# SPM.net
KiCad netlist of a schematic drawn in EAGLE
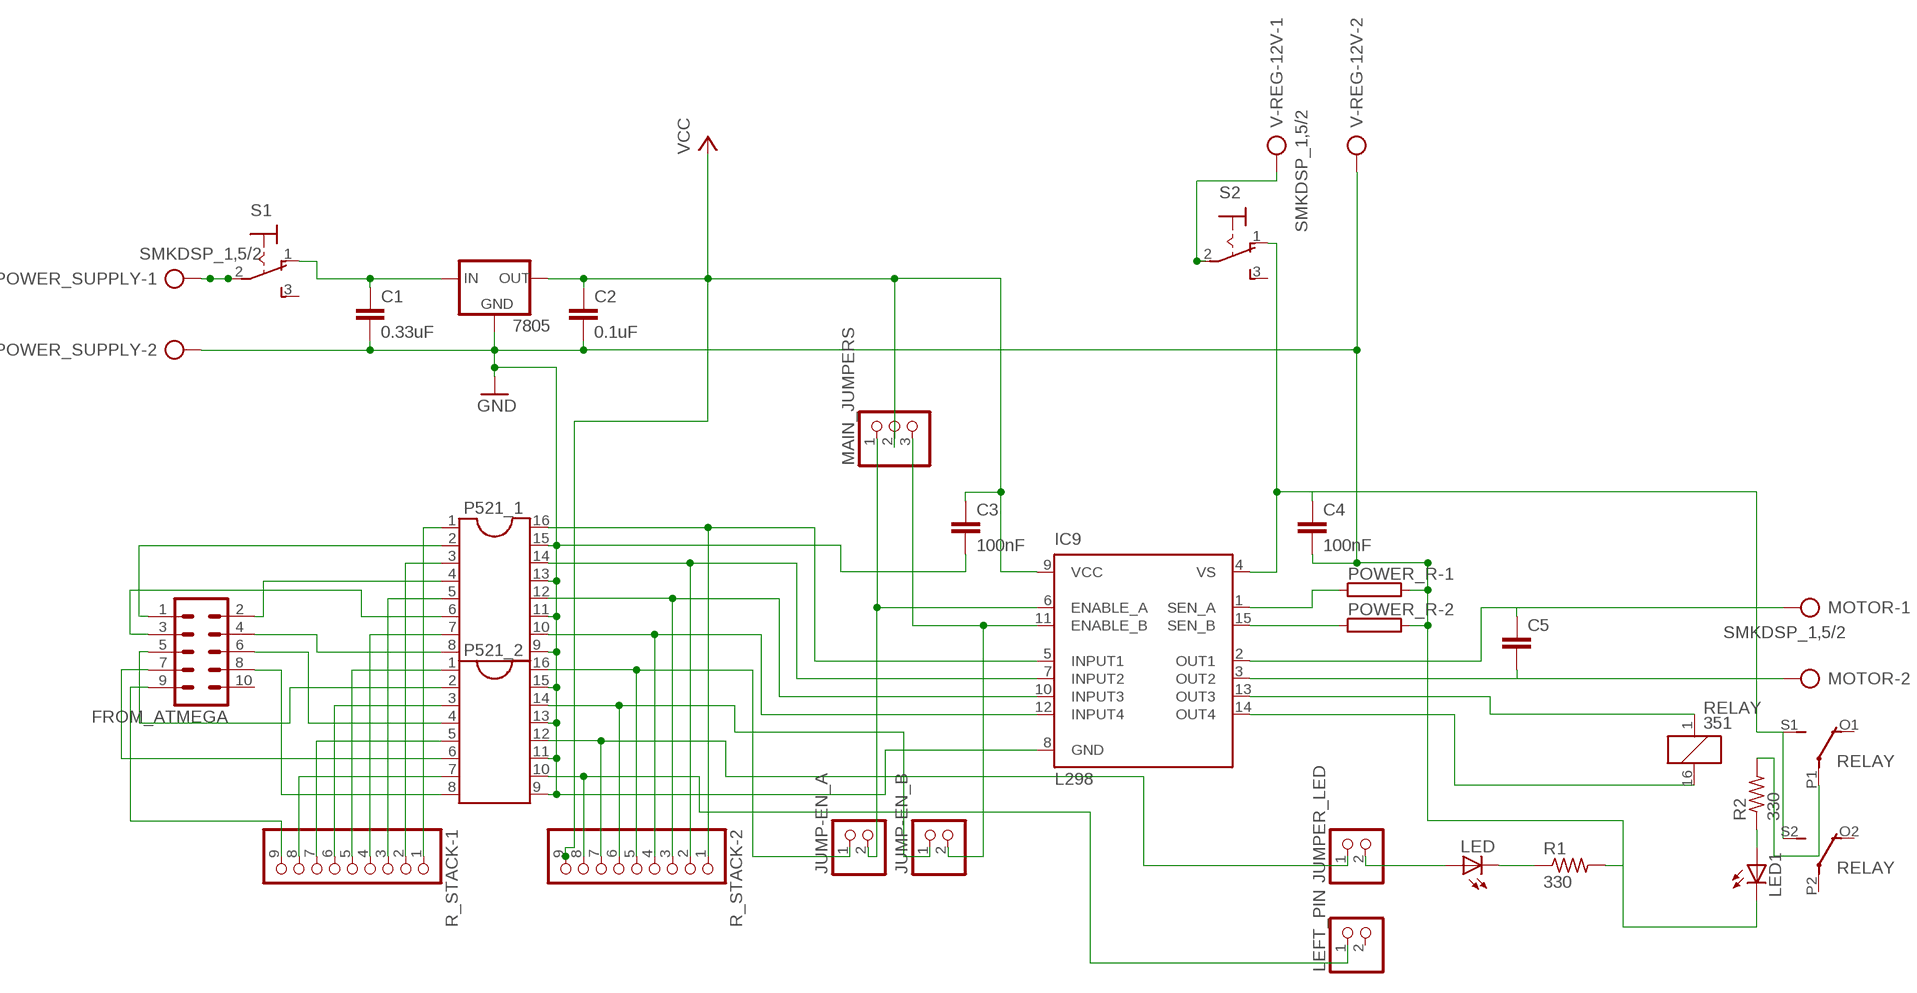
[diagram p0: schematic, sheet 1]

(export (version "E")
  (design (tool "Eeschema 10.0.6"))
  (components
    (comp (ref "7805")
      (value "78XXS")
      (footprint "eagle-import:78XXS")
      (libsource (lib "eagle-import") (part "78XXS"))
    )
    (comp (ref "C1")
      (value "0.33uF")
      (footprint "eagle-import:C2.5-3")
      (libsource (lib "eagle-import") (part "C2,5-3"))
    )
    (comp (ref "C2")
      (value "0.1uF")
      (footprint "eagle-import:C2.5-3")
      (libsource (lib "eagle-import") (part "C2,5-3"))
    )
    (comp (ref "C3")
      (value "100nF")
      (footprint "eagle-import:C2.5-3")
      (libsource (lib "eagle-import") (part "C2,5-3"))
    )
    (comp (ref "C4")
      (value "100nF")
      (footprint "eagle-import:C2.5-3")
      (libsource (lib "eagle-import") (part "C2,5-3"))
    )
    (comp (ref "C5")
      (value "C2,5-3")
      (footprint "eagle-import:C2.5-3")
      (libsource (lib "eagle-import") (part "C2,5-3"))
    )
    (comp (ref "FROM_ATMEGA")
      (value "ML10")
      (footprint "eagle-import:ML10")
      (libsource (lib "eagle-import") (part "ML10"))
    )
    (comp (ref "IC9")
      (value "L298")
      (footprint "eagle-import:MULTIWATT-15")
      (fields (field (name "MPN") "L298N"))
      (libsource (lib "eagle-import") (part "L298"))
    )
    (comp (ref "JUMP-EN_A")
      (value "PINHD-1X2")
      (footprint "eagle-import:1X02")
      (libsource (lib "eagle-import") (part "PINHD-1X2"))
    )
    (comp (ref "JUMP-EN_B")
      (value "PINHD-1X2")
      (footprint "eagle-import:1X02")
      (libsource (lib "eagle-import") (part "PINHD-1X2"))
    )
    (comp (ref "JUMPER_LED")
      (value "PINHD-1X2")
      (footprint "eagle-import:1X02")
      (libsource (lib "eagle-import") (part "PINHD-1X2"))
    )
    (comp (ref "LED")
      (value "LED10MM")
      (footprint "eagle-import:LED10MM")
      (libsource (lib "eagle-import") (part "LED10MM"))
    )
    (comp (ref "LED1")
      (value "LED10MM")
      (footprint "eagle-import:LED10MM")
      (libsource (lib "eagle-import") (part "LED10MM"))
    )
    (comp (ref "LEFT_PIN")
      (value "PINHD-1X2")
      (footprint "eagle-import:1X02")
      (libsource (lib "eagle-import") (part "PINHD-1X2"))
    )
    (comp (ref "MAIN_JUMPERS")
      (value "PINHD-1X3")
      (footprint "eagle-import:1X03")
      (libsource (lib "eagle-import") (part "PINHD-1X3"))
    )
    (comp (ref "MOTOR")
      (value "SMKDSP_1,5/2")
      (footprint "eagle-import:SMKDSP_1,5_2")
      (fields (field (name "MF") "FARNELL") (field (name "MPN") "1733570"))
      (libsource (lib "eagle-import") (part "SMKDSP_1,5/2"))
    )
    (comp (ref "P521_1")
      (value "DIL16")
      (footprint "eagle-import:DIL16")
      (libsource (lib "eagle-import") (part "DIL16"))
    )
    (comp (ref "P521_2")
      (value "DIL16")
      (footprint "eagle-import:DIL16")
      (libsource (lib "eagle-import") (part "DIL16"))
    )
    (comp (ref "POWER_R-1")
      (value "RHPS932")
      (footprint "eagle-import:HPS932")
      (libsource (lib "eagle-import") (part "RHPS932"))
    )
    (comp (ref "POWER_R-2")
      (value "RHPS932")
      (footprint "eagle-import:HPS932")
      (fields (field (name "OC_FARNELL") "unknown") (field (name "OC_NEWARK") "unknown"))
      (libsource (lib "eagle-import") (part "RHPS932"))
    )
    (comp (ref "POWER_SUPPLY")
      (value "SMKDSP_1,5/2")
      (footprint "eagle-import:SMKDSP_1,5_2")
      (fields (field (name "MF") "FARNELL") (field (name "MPN") "1733570"))
      (libsource (lib "eagle-import") (part "SMKDSP_1,5/2"))
    )
    (comp (ref "R1")
      (value "330")
      (footprint "eagle-import:0204_7")
      (libsource (lib "eagle-import") (part "R-US_0204/7"))
    )
    (comp (ref "R2")
      (value "330")
      (footprint "eagle-import:0204_7")
      (libsource (lib "eagle-import") (part "R-US_0204/7"))
    )
    (comp (ref "RELAY")
      (value "351")
      (footprint "eagle-import:351")
      (libsource (lib "eagle-import") (part "351"))
    )
    (comp (ref "R_STACK-1")
      (value "PINHD-1X9")
      (footprint "eagle-import:1X09")
      (libsource (lib "eagle-import") (part "PINHD-1X9"))
    )
    (comp (ref "R_STACK-2")
      (value "PINHD-1X9")
      (footprint "eagle-import:1X09")
      (libsource (lib "eagle-import") (part "PINHD-1X9"))
    )
    (comp (ref "S1")
      (value "320-916")
      (footprint "eagle-import:320-916")
      (libsource (lib "eagle-import") (part "320-916"))
    )
    (comp (ref "S2")
      (value "320-916")
      (footprint "eagle-import:320-916")
      (libsource (lib "eagle-import") (part "320-916"))
    )
    (comp (ref "V-REG-12V")
      (value "SMKDSP_1,5/2")
      (footprint "eagle-import:SMKDSP_1,5_2")
      (fields (field (name "MF") "FARNELL") (field (name "MPN") "1733570"))
      (libsource (lib "eagle-import") (part "SMKDSP_1,5/2"))
    )
  )
  (nets
    (net (code "1") (name "GND") (class "Default")
      (node (ref "7805") (pin "GND") (pinfunction "GND_GND") (pintype "input"))
      (node (ref "C1") (pin "2") (pinfunction "2_2") (pintype "passive"))
      (node (ref "C2") (pin "2") (pinfunction "2_2") (pintype "passive"))
      (node (ref "C3") (pin "2") (pinfunction "2_2") (pintype "passive"))
      (node (ref "C4") (pin "2") (pinfunction "2_2") (pintype "passive"))
      (node (ref "IC9") (pin "8") (pinfunction "GND_8") (pintype "power_in"))
      (node (ref "LED1") (pin "K") (pinfunction "C_K") (pintype "passive"))
      (node (ref "P521_1") (pin "11") (pinfunction "11_11") (pintype "passive"))
      (node (ref "P521_1") (pin "13") (pinfunction "13_13") (pintype "passive"))
      (node (ref "P521_1") (pin "15") (pinfunction "15_15") (pintype "passive"))
      (node (ref "P521_1") (pin "9") (pinfunction "9_9") (pintype "passive"))
      (node (ref "P521_2") (pin "11") (pinfunction "11_11") (pintype "passive"))
      (node (ref "P521_2") (pin "13") (pinfunction "13_13") (pintype "passive"))
      (node (ref "P521_2") (pin "15") (pinfunction "15_15") (pintype "passive"))
      (node (ref "P521_2") (pin "9") (pinfunction "9_9") (pintype "passive"))
      (node (ref "POWER_R-1") (pin "2") (pinfunction "2_2") (pintype "passive"))
      (node (ref "POWER_R-2") (pin "2") (pinfunction "2_2") (pintype "passive"))
      (node (ref "POWER_SUPPLY") (pin "2") (pinfunction "KL_2") (pintype "passive"))
      (node (ref "R1") (pin "2") (pinfunction "2_2") (pintype "passive"))
      (node (ref "V-REG-12V") (pin "2") (pinfunction "KL_2") (pintype "passive"))
    )
    (net (code "2") (name "Net-(FROM_ATMEGA-Pad1)") (class "Default")
      (node (ref "FROM_ATMEGA") (pin "1") (pinfunction "1_1") (pintype "passive"))
      (node (ref "P521_1") (pin "2") (pinfunction "2_2") (pintype "passive"))
    )
    (net (code "3") (name "Net-(FROM_ATMEGA-Pad2)") (class "Default")
      (node (ref "FROM_ATMEGA") (pin "2") (pinfunction "2_2") (pintype "passive"))
      (node (ref "P521_1") (pin "4") (pinfunction "4_4") (pintype "passive"))
    )
    (net (code "4") (name "Net-(FROM_ATMEGA-Pad3)") (class "Default")
      (node (ref "FROM_ATMEGA") (pin "3") (pinfunction "3_3") (pintype "passive"))
      (node (ref "P521_1") (pin "6") (pinfunction "6_6") (pintype "passive"))
    )
    (net (code "5") (name "Net-(FROM_ATMEGA-Pad4)") (class "Default")
      (node (ref "FROM_ATMEGA") (pin "4") (pinfunction "4_4") (pintype "passive"))
      (node (ref "P521_1") (pin "8") (pinfunction "8_8") (pintype "passive"))
    )
    (net (code "6") (name "Net-(FROM_ATMEGA-Pad5)") (class "Default")
      (node (ref "FROM_ATMEGA") (pin "5") (pinfunction "5_5") (pintype "passive"))
      (node (ref "P521_2") (pin "2") (pinfunction "2_2") (pintype "passive"))
    )
    (net (code "7") (name "Net-(FROM_ATMEGA-Pad6)") (class "Default")
      (node (ref "FROM_ATMEGA") (pin "6") (pinfunction "6_6") (pintype "passive"))
      (node (ref "P521_2") (pin "4") (pinfunction "4_4") (pintype "passive"))
    )
    (net (code "8") (name "Net-(FROM_ATMEGA-Pad7)") (class "Default")
      (node (ref "FROM_ATMEGA") (pin "7") (pinfunction "7_7") (pintype "passive"))
      (node (ref "P521_2") (pin "6") (pinfunction "6_6") (pintype "passive"))
    )
    (net (code "9") (name "Net-(FROM_ATMEGA-Pad8)") (class "Default")
      (node (ref "FROM_ATMEGA") (pin "8") (pinfunction "8_8") (pintype "passive"))
      (node (ref "P521_2") (pin "8") (pinfunction "8_8") (pintype "passive"))
    )
    (net (code "10") (name "Net-(FROM_ATMEGA-Pad9)") (class "Default")
      (node (ref "FROM_ATMEGA") (pin "9") (pinfunction "9_9") (pintype "passive"))
      (node (ref "R_STACK-1") (pin "9") (pinfunction "9_9") (pintype "passive"))
    )
    (net (code "11") (name "Net-(IC9-ENABLE_A)") (class "Default")
      (node (ref "IC9") (pin "6") (pinfunction "ENABLE_A_6") (pintype "input"))
      (node (ref "JUMP-EN_A") (pin "2") (pinfunction "2_2") (pintype "passive"))
      (node (ref "MAIN_JUMPERS") (pin "1") (pinfunction "1_1") (pintype "passive"))
    )
    (net (code "12") (name "Net-(IC9-ENABLE_B)") (class "Default")
      (node (ref "IC9") (pin "11") (pinfunction "ENABLE_B_11") (pintype "input"))
      (node (ref "JUMP-EN_B") (pin "2") (pinfunction "2_2") (pintype "passive"))
      (node (ref "MAIN_JUMPERS") (pin "3") (pinfunction "3_3") (pintype "passive"))
    )
    (net (code "13") (name "Net-(IC9-INPUT1)") (class "Default")
      (node (ref "IC9") (pin "5") (pinfunction "INPUT1_5") (pintype "input"))
      (node (ref "P521_1") (pin "16") (pinfunction "16_16") (pintype "passive"))
      (node (ref "R_STACK-2") (pin "1") (pinfunction "1_1") (pintype "passive"))
    )
    (net (code "14") (name "Net-(IC9-INPUT2)") (class "Default")
      (node (ref "IC9") (pin "7") (pinfunction "INPUT2_7") (pintype "input"))
      (node (ref "P521_1") (pin "14") (pinfunction "14_14") (pintype "passive"))
      (node (ref "R_STACK-2") (pin "2") (pinfunction "2_2") (pintype "passive"))
    )
    (net (code "15") (name "Net-(IC9-INPUT3)") (class "Default")
      (node (ref "IC9") (pin "10") (pinfunction "INPUT3_10") (pintype "input"))
      (node (ref "P521_1") (pin "12") (pinfunction "12_12") (pintype "passive"))
      (node (ref "R_STACK-2") (pin "3") (pinfunction "3_3") (pintype "passive"))
    )
    (net (code "16") (name "Net-(IC9-INPUT4)") (class "Default")
      (node (ref "IC9") (pin "12") (pinfunction "INPUT4_12") (pintype "input"))
      (node (ref "P521_1") (pin "10") (pinfunction "10_10") (pintype "passive"))
      (node (ref "R_STACK-2") (pin "4") (pinfunction "4_4") (pintype "passive"))
    )
    (net (code "17") (name "Net-(IC9-OUT1)") (class "Default")
      (node (ref "C5") (pin "1") (pinfunction "1_1") (pintype "passive"))
      (node (ref "IC9") (pin "2") (pinfunction "OUT1_2") (pintype "output"))
      (node (ref "MOTOR") (pin "1") (pinfunction "KL_1") (pintype "passive"))
    )
    (net (code "18") (name "Net-(IC9-OUT2)") (class "Default")
      (node (ref "C5") (pin "2") (pinfunction "2_2") (pintype "passive"))
      (node (ref "IC9") (pin "3") (pinfunction "OUT2_3") (pintype "output"))
      (node (ref "MOTOR") (pin "2") (pinfunction "KL_2") (pintype "passive"))
    )
    (net (code "19") (name "Net-(IC9-OUT3)") (class "Default")
      (node (ref "IC9") (pin "13") (pinfunction "OUT3_13") (pintype "output"))
      (node (ref "RELAY") (pin "1") (pinfunction "1_1") (pintype "passive"))
    )
    (net (code "20") (name "Net-(IC9-OUT4)") (class "Default")
      (node (ref "IC9") (pin "14") (pinfunction "OUT4_14") (pintype "output"))
      (node (ref "RELAY") (pin "16") (pinfunction "2_16") (pintype "passive"))
    )
    (net (code "21") (name "Net-(IC9-SEN_A)") (class "Default")
      (node (ref "IC9") (pin "1") (pinfunction "SEN_A_1") (pintype "input"))
      (node (ref "POWER_R-1") (pin "1") (pinfunction "1_1") (pintype "passive"))
    )
    (net (code "22") (name "Net-(IC9-SEN_B)") (class "Default")
      (node (ref "IC9") (pin "15") (pinfunction "SEN_B_15") (pintype "input"))
      (node (ref "POWER_R-2") (pin "1") (pinfunction "1_1") (pintype "passive"))
    )
    (net (code "23") (name "Net-(IC9-VS)") (class "Default")
      (node (ref "C4") (pin "1") (pinfunction "1_1") (pintype "passive"))
      (node (ref "IC9") (pin "4") (pinfunction "VS_4") (pintype "power_in"))
      (node (ref "RELAY") (pin "S1") (pinfunction "S_S1") (pintype "passive"))
      (node (ref "RELAY") (pin "S2") (pinfunction "S_S2") (pintype "passive"))
      (node (ref "S2") (pin "1") (pinfunction "O_1") (pintype "passive"))
    )
    (net (code "24") (name "Net-(JUMP-EN_A-Pad1)") (class "Default")
      (node (ref "JUMP-EN_A") (pin "1") (pinfunction "1_1") (pintype "passive"))
      (node (ref "P521_2") (pin "16") (pinfunction "16_16") (pintype "passive"))
      (node (ref "R_STACK-2") (pin "5") (pinfunction "5_5") (pintype "passive"))
    )
    (net (code "25") (name "Net-(JUMP-EN_B-Pad1)") (class "Default")
      (node (ref "JUMP-EN_B") (pin "1") (pinfunction "1_1") (pintype "passive"))
      (node (ref "P521_2") (pin "14") (pinfunction "14_14") (pintype "passive"))
      (node (ref "R_STACK-2") (pin "6") (pinfunction "6_6") (pintype "passive"))
    )
    (net (code "26") (name "Net-(JUMPER_LED-Pad1)") (class "Default")
      (node (ref "JUMPER_LED") (pin "1") (pinfunction "1_1") (pintype "passive"))
      (node (ref "P521_2") (pin "12") (pinfunction "12_12") (pintype "passive"))
      (node (ref "R_STACK-2") (pin "7") (pinfunction "7_7") (pintype "passive"))
    )
    (net (code "27") (name "Net-(JUMPER_LED-Pad2)") (class "Default")
      (node (ref "JUMPER_LED") (pin "2") (pinfunction "2_2") (pintype "passive"))
      (node (ref "LED") (pin "A") (pinfunction "A_A") (pintype "passive"))
    )
    (net (code "28") (name "Net-(LED-C)") (class "Default")
      (node (ref "LED") (pin "K") (pinfunction "C_K") (pintype "passive"))
      (node (ref "R1") (pin "1") (pinfunction "1_1") (pintype "passive"))
    )
    (net (code "29") (name "Net-(LED1-PadA)") (class "Default")
      (node (ref "LED1") (pin "A") (pinfunction "A_A") (pintype "passive"))
      (node (ref "R2") (pin "1") (pinfunction "1_1") (pintype "passive"))
    )
    (net (code "30") (name "Net-(LEFT_PIN-Pad1)") (class "Default")
      (node (ref "LEFT_PIN") (pin "1") (pinfunction "1_1") (pintype "passive"))
      (node (ref "P521_2") (pin "10") (pinfunction "10_10") (pintype "passive"))
      (node (ref "R_STACK-2") (pin "8") (pinfunction "8_8") (pintype "passive"))
    )
    (net (code "31") (name "Net-(P521_1-Pad1)") (class "Default")
      (node (ref "P521_1") (pin "1") (pinfunction "1_1") (pintype "passive"))
      (node (ref "R_STACK-1") (pin "1") (pinfunction "1_1") (pintype "passive"))
    )
    (net (code "32") (name "Net-(P521_1-Pad3)") (class "Default")
      (node (ref "P521_1") (pin "3") (pinfunction "3_3") (pintype "passive"))
      (node (ref "R_STACK-1") (pin "2") (pinfunction "2_2") (pintype "passive"))
    )
    (net (code "33") (name "Net-(P521_1-Pad5)") (class "Default")
      (node (ref "P521_1") (pin "5") (pinfunction "5_5") (pintype "passive"))
      (node (ref "R_STACK-1") (pin "3") (pinfunction "3_3") (pintype "passive"))
    )
    (net (code "34") (name "Net-(P521_1-Pad7)") (class "Default")
      (node (ref "P521_1") (pin "7") (pinfunction "7_7") (pintype "passive"))
      (node (ref "R_STACK-1") (pin "4") (pinfunction "4_4") (pintype "passive"))
    )
    (net (code "35") (name "Net-(P521_2-Pad1)") (class "Default")
      (node (ref "P521_2") (pin "1") (pinfunction "1_1") (pintype "passive"))
      (node (ref "R_STACK-1") (pin "5") (pinfunction "5_5") (pintype "passive"))
    )
    (net (code "36") (name "Net-(P521_2-Pad3)") (class "Default")
      (node (ref "P521_2") (pin "3") (pinfunction "3_3") (pintype "passive"))
      (node (ref "R_STACK-1") (pin "6") (pinfunction "6_6") (pintype "passive"))
    )
    (net (code "37") (name "Net-(P521_2-Pad5)") (class "Default")
      (node (ref "P521_2") (pin "5") (pinfunction "5_5") (pintype "passive"))
      (node (ref "R_STACK-1") (pin "7") (pinfunction "7_7") (pintype "passive"))
    )
    (net (code "38") (name "Net-(P521_2-Pad7)") (class "Default")
      (node (ref "P521_2") (pin "7") (pinfunction "7_7") (pintype "passive"))
      (node (ref "R_STACK-1") (pin "8") (pinfunction "8_8") (pintype "passive"))
    )
    (net (code "39") (name "Net-(POWER_SUPPLYA-KL)") (class "Default")
      (node (ref "POWER_SUPPLY") (pin "1") (pinfunction "KL_1") (pintype "passive"))
      (node (ref "S1") (pin "2") (pinfunction "P_2") (pintype "passive"))
    )
    (net (code "40") (name "Net-(RELAYB-P)") (class "Default")
      (node (ref "R2") (pin "2") (pinfunction "2_2") (pintype "passive"))
      (node (ref "RELAY") (pin "P1") (pinfunction "P_P1") (pintype "passive"))
    )
    (net (code "41") (name "Net-(S1-O)") (class "Default")
      (node (ref "7805") (pin "IN") (pinfunction "IN_IN") (pintype "input"))
      (node (ref "C1") (pin "1") (pinfunction "1_1") (pintype "passive"))
      (node (ref "S1") (pin "1") (pinfunction "O_1") (pintype "passive"))
    )
    (net (code "42") (name "Net-(S2-P)") (class "Default")
      (node (ref "S2") (pin "2") (pinfunction "P_2") (pintype "passive"))
      (node (ref "V-REG-12V") (pin "1") (pinfunction "KL_1") (pintype "passive"))
    )
    (net (code "43") (name "VCC") (class "Default")
      (node (ref "7805") (pin "OUT") (pinfunction "OUT_OUT") (pintype "passive"))
      (node (ref "C2") (pin "1") (pinfunction "1_1") (pintype "passive"))
      (node (ref "C3") (pin "1") (pinfunction "1_1") (pintype "passive"))
      (node (ref "IC9") (pin "9") (pinfunction "VCC_9") (pintype "power_in"))
      (node (ref "MAIN_JUMPERS") (pin "2") (pinfunction "2_2") (pintype "passive"))
      (node (ref "R_STACK-2") (pin "9") (pinfunction "9_9") (pintype "passive"))
    )
    (net (code "44") (name "unconnected-(FROM_ATMEGA-Pad10)") (class "Default")
      (node (ref "FROM_ATMEGA") (pin "10") (pinfunction "10_10") (pintype "passive"))
    )
    (net (code "45") (name "unconnected-(LEFT_PIN-Pad2)") (class "Default")
      (node (ref "LEFT_PIN") (pin "2") (pinfunction "2_2") (pintype "passive"))
    )
    (net (code "46") (name "unconnected-(RELAYB-O-PadO1)") (class "Default")
      (node (ref "RELAY") (pin "O1") (pinfunction "O_O1") (pintype "passive"))
    )
    (net (code "47") (name "unconnected-(RELAYC-O-PadO2)") (class "Default")
      (node (ref "RELAY") (pin "O2") (pinfunction "O_O2") (pintype "passive"))
    )
    (net (code "48") (name "unconnected-(RELAYC-P-PadP2)") (class "Default")
      (node (ref "RELAY") (pin "P2") (pinfunction "P_P2") (pintype "passive"))
    )
    (net (code "49") (name "unconnected-(S1-S-Pad3)") (class "Default")
      (node (ref "S1") (pin "3") (pinfunction "S_3") (pintype "passive"))
    )
    (net (code "50") (name "unconnected-(S2-S-Pad3)") (class "Default")
      (node (ref "S2") (pin "3") (pinfunction "S_3") (pintype "passive"))
    )
  )
)
